# S02.net
KiCad netlist of a schematic drawn in Altium Designer
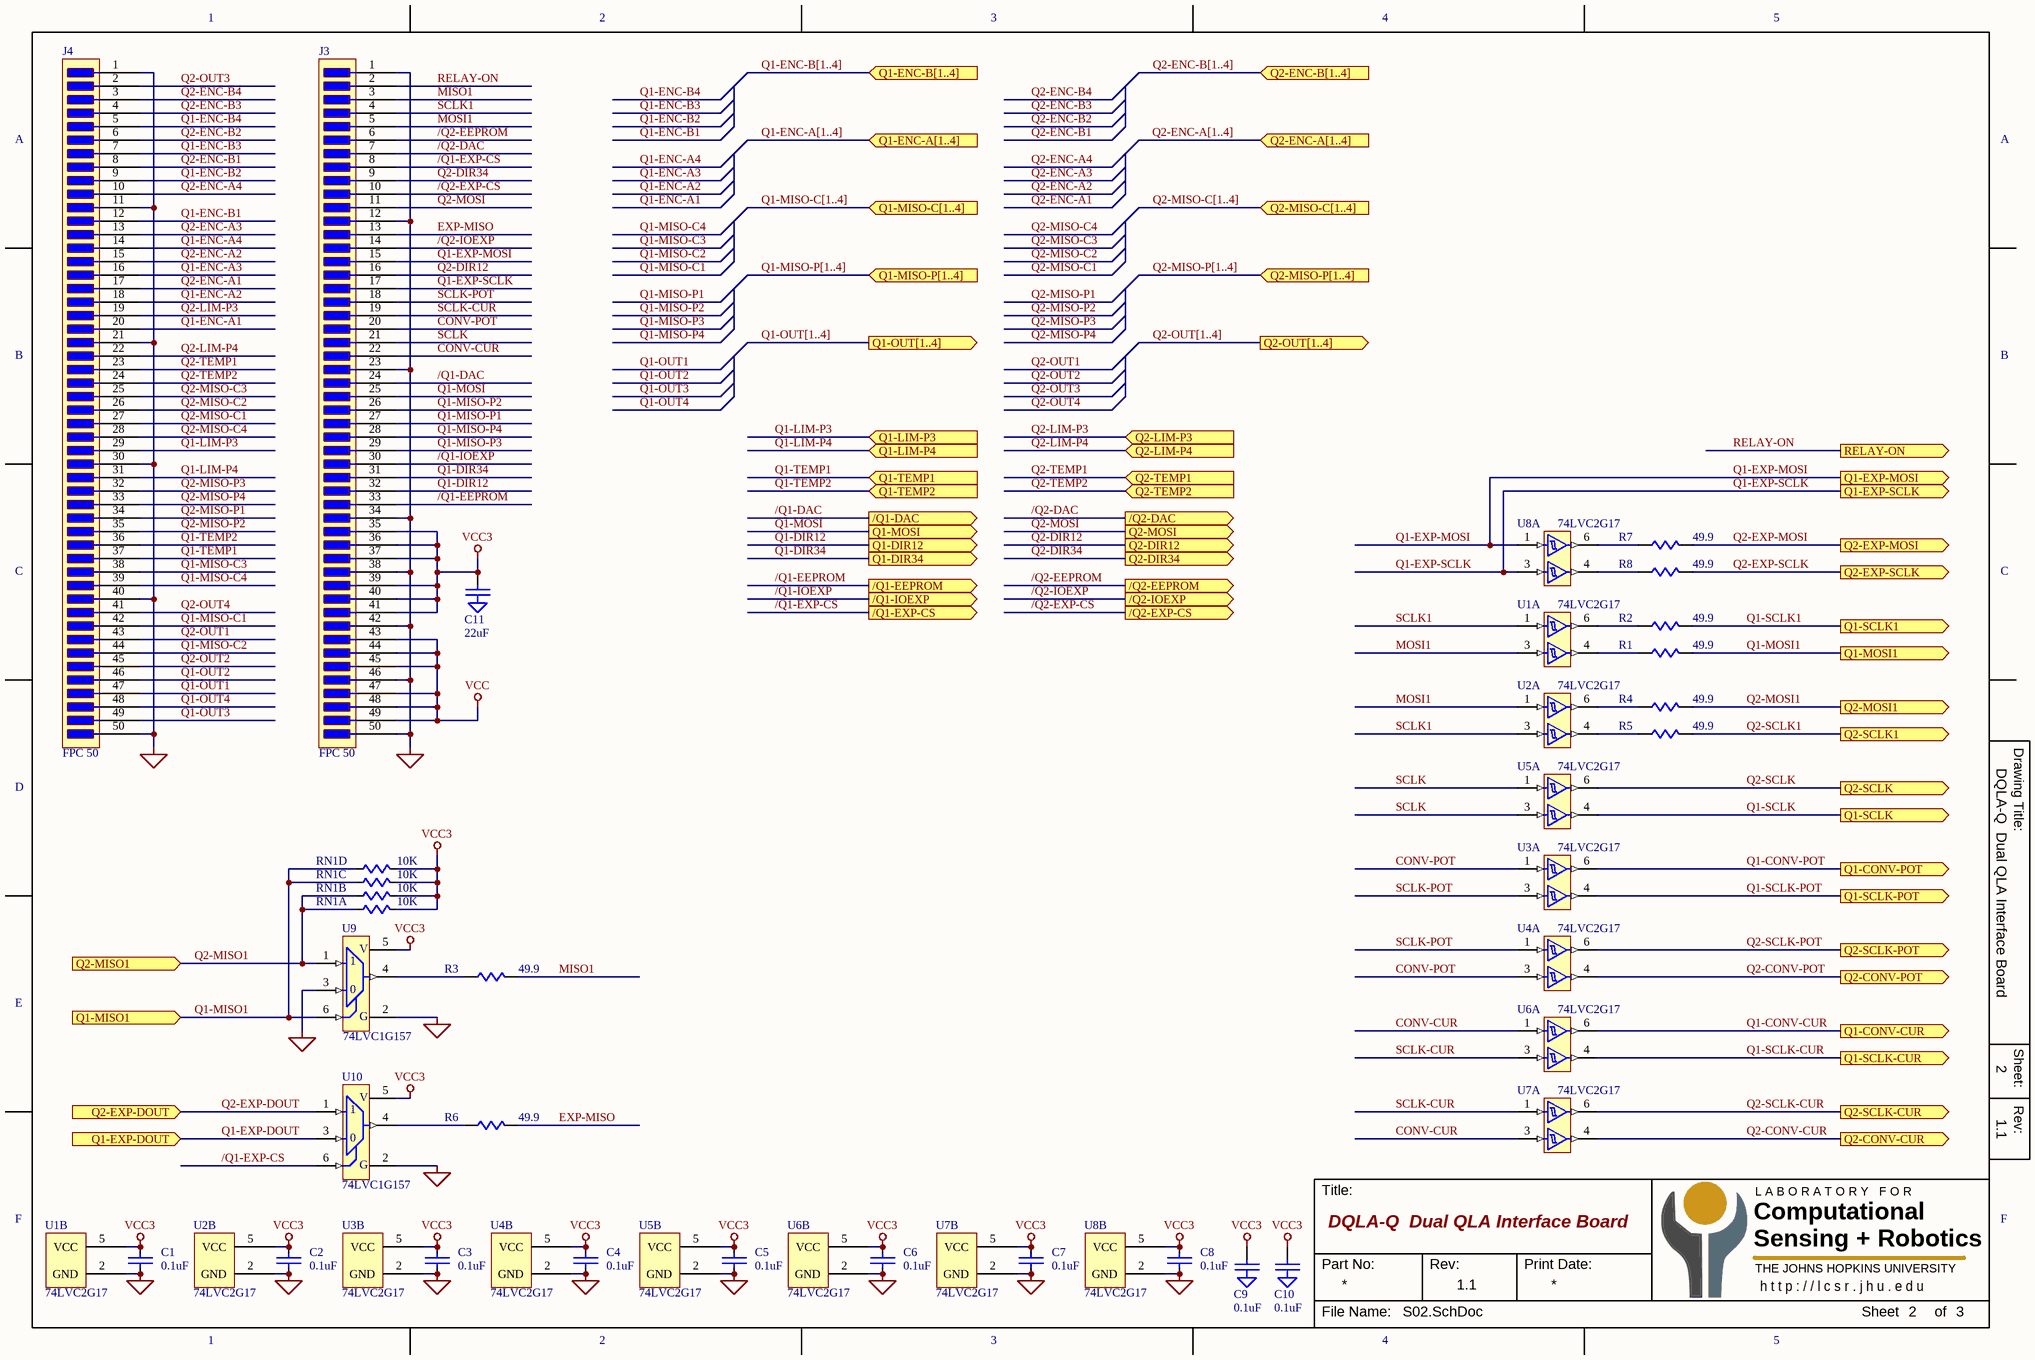
[diagram p0: S02.SchDoc]

(export (version "E")
  (design (tool "Eeschema 10.0.6"))
  (components
    (comp (ref "C1") (value "0.1uF") (footprint "C0402") (libsource (lib "LibJHU") (part "CAP")))
    (comp (ref "C2") (value "0.1uF") (footprint "C0402") (libsource (lib "LibJHU") (part "CAP")))
    (comp (ref "C3") (value "0.1uF") (footprint "C0402") (libsource (lib "LibJHU") (part "CAP")))
    (comp (ref "C4") (value "0.1uF") (footprint "C0402") (libsource (lib "LibJHU") (part "CAP")))
    (comp (ref "C5") (value "0.1uF") (footprint "C0402") (libsource (lib "LibJHU") (part "CAP")))
    (comp (ref "C6") (value "0.1uF") (footprint "C0402") (libsource (lib "LibJHU") (part "CAP")))
    (comp (ref "C7") (value "0.1uF") (footprint "C0402") (libsource (lib "LibJHU") (part "CAP")))
    (comp (ref "C8") (value "0.1uF") (footprint "C0402") (libsource (lib "LibJHU") (part "CAP")))
    (comp (ref "C9") (value "0.1uF") (footprint "C0402") (libsource (lib "LibJHU") (part "CAP-GND")))
    (comp (ref "C10") (value "0.1uF") (footprint "C0402") (libsource (lib "LibJHU") (part "CAP-GND")))
    (comp (ref "C11") (value "22uF") (footprint "C0805") (libsource (lib "LibJHU") (part "CAP-GND")))
    (comp (ref "J3")
      (value "FPC 50")
      (footprint "CONN-XF3M1-5015-1B")
      (libsource (lib "LibJHU") (part "FPC 50"))
    )
    (comp (ref "J4")
      (value "FPC 50")
      (footprint "CONN-XF3M1-5015-1B")
      (libsource (lib "LibJHU") (part "FPC 50"))
    )
    (comp (ref "R1") (value "49.9") (footprint "R0402") (libsource (lib "LibJHU") (part "R")))
    (comp (ref "R2") (value "49.9") (footprint "R0402") (libsource (lib "LibJHU") (part "R")))
    (comp (ref "R3") (value "49.9") (footprint "R0402") (libsource (lib "LibJHU") (part "R")))
    (comp (ref "R4") (value "49.9") (footprint "R0402") (libsource (lib "LibJHU") (part "R")))
    (comp (ref "R5") (value "49.9") (footprint "R0402") (libsource (lib "LibJHU") (part "R")))
    (comp (ref "R6") (value "49.9") (footprint "R0402") (libsource (lib "LibJHU") (part "R")))
    (comp (ref "R7") (value "49.9") (footprint "R0402") (libsource (lib "LibJHU") (part "R")))
    (comp (ref "R8") (value "49.9") (footprint "R0402") (libsource (lib "LibJHU") (part "R")))
    (comp (ref "RN1")
      (value "10K")
      (footprint "RN-742C083")
      (libsource (lib "LibJHU") (part "RN-DISC-SM-4X"))
    )
    (comp (ref "U1")
      (value "74LVC2G17")
      (footprint "SC70-6")
      (description "NC7WZ17")
      (libsource (lib "LibJHU") (part "2G17-2"))
    )
    (comp (ref "U2")
      (value "74LVC2G17")
      (footprint "SC70-6")
      (description "NC7WZ17")
      (libsource (lib "LibJHU") (part "2G17-2"))
    )
    (comp (ref "U3")
      (value "74LVC2G17")
      (footprint "SC70-6")
      (description "NC7WZ17")
      (libsource (lib "LibJHU") (part "2G17-2"))
    )
    (comp (ref "U4")
      (value "74LVC2G17")
      (footprint "SC70-6")
      (description "NC7WZ17")
      (libsource (lib "LibJHU") (part "2G17-2"))
    )
    (comp (ref "U5")
      (value "74LVC2G17")
      (footprint "SC70-6")
      (description "NC7WZ17")
      (libsource (lib "LibJHU") (part "2G17-2"))
    )
    (comp (ref "U6")
      (value "74LVC2G17")
      (footprint "SC70-6")
      (description "NC7WZ17")
      (libsource (lib "LibJHU") (part "2G17-2"))
    )
    (comp (ref "U7")
      (value "74LVC2G17")
      (footprint "SC70-6")
      (description "NC7WZ17")
      (libsource (lib "LibJHU") (part "2G17-2"))
    )
    (comp (ref "U8")
      (value "74LVC2G17")
      (footprint "SC70-6")
      (description "NC7WZ17")
      (libsource (lib "LibJHU") (part "2G17-2"))
    )
    (comp (ref "U9") (value "74LVC1G157") (footprint "SC70-6") (libsource (lib "LibJHU") (part "1G157")))
    (comp (ref "U10") (value "74LVC1G157") (footprint "SC70-6") (libsource (lib "LibJHU") (part "1G157")))
  )
  (nets
    (net (code "1") (name "/CONV-CUR") (class "Default")
      (node (ref "J3") (pin "22") (pinfunction "22_22") (pintype "passive"))
      (node (ref "U6") (pin "1") (pintype "input"))
      (node (ref "U7") (pin "3") (pintype "input"))
    )
    (net (code "2") (name "/CONV-POT") (class "Default")
      (node (ref "J3") (pin "20") (pinfunction "20_20") (pintype "passive"))
      (node (ref "U3") (pin "1") (pintype "input"))
      (node (ref "U4") (pin "3") (pintype "input"))
    )
    (net (code "3") (name "/EXP-MISO") (class "Default")
      (node (ref "J3") (pin "13") (pinfunction "13_13") (pintype "passive"))
      (node (ref "R6") (pin "2") (pinfunction "2_2") (pintype "passive"))
    )
    (net (code "4") (name "/MISO1") (class "Default")
      (node (ref "J3") (pin "3") (pinfunction "3_3") (pintype "passive"))
      (node (ref "R3") (pin "2") (pinfunction "2_2") (pintype "passive"))
    )
    (net (code "5") (name "/MOSI1") (class "Default")
      (node (ref "J3") (pin "5") (pinfunction "5_5") (pintype "passive"))
      (node (ref "U1") (pin "3") (pintype "input"))
      (node (ref "U2") (pin "1") (pintype "input"))
    )
    (net (code "6") (name "/Q1-CONV-CUR") (class "Default") (node (ref "U6") (pin "6") (pintype "output")))
    (net (code "7") (name "/Q1-CONV-POT") (class "Default") (node (ref "U3") (pin "6") (pintype "output")))
    (net (code "8") (name "/Q1-DIR12") (class "Default")
      (node (ref "J3") (pin "32") (pinfunction "32_32") (pintype "passive"))
    )
    (net (code "9") (name "/Q1-DIR34") (class "Default")
      (node (ref "J3") (pin "31") (pinfunction "31_31") (pintype "passive"))
    )
    (net (code "10") (name "/Q1-ENC-A1") (class "Default")
      (node (ref "J4") (pin "20") (pinfunction "20_20") (pintype "passive"))
    )
    (net (code "11") (name "/Q1-ENC-A2") (class "Default")
      (node (ref "J4") (pin "18") (pinfunction "18_18") (pintype "passive"))
    )
    (net (code "12") (name "/Q1-ENC-A3") (class "Default")
      (node (ref "J4") (pin "16") (pinfunction "16_16") (pintype "passive"))
    )
    (net (code "13") (name "/Q1-ENC-A4") (class "Default")
      (node (ref "J4") (pin "14") (pinfunction "14_14") (pintype "passive"))
    )
    (net (code "15") (name "/Q1-ENC-B1") (class "Default")
      (node (ref "J4") (pin "12") (pinfunction "12_12") (pintype "passive"))
    )
    (net (code "16") (name "/Q1-ENC-B2") (class "Default")
      (node (ref "J4") (pin "9") (pinfunction "9_9") (pintype "passive"))
    )
    (net (code "17") (name "/Q1-ENC-B3") (class "Default")
      (node (ref "J4") (pin "7") (pinfunction "7_7") (pintype "passive"))
    )
    (net (code "18") (name "/Q1-ENC-B4") (class "Default")
      (node (ref "J4") (pin "5") (pinfunction "5_5") (pintype "passive"))
    )
    (net (code "20") (name "/Q1-EXP-DOUT") (class "Default") (node (ref "U10") (pin "3") (pintype "input")))
    (net (code "21") (name "/Q1-EXP-MOSI") (class "Default")
      (node (ref "J3") (pin "15") (pinfunction "15_15") (pintype "passive"))
      (node (ref "U8") (pin "1") (pintype "input"))
    )
    (net (code "22") (name "/Q1-EXP-SCLK") (class "Default")
      (node (ref "J3") (pin "17") (pinfunction "17_17") (pintype "passive"))
      (node (ref "U8") (pin "3") (pintype "input"))
    )
    (net (code "23") (name "/Q1-LIM-P3") (class "Default")
      (node (ref "J4") (pin "29") (pinfunction "29_29") (pintype "passive"))
    )
    (net (code "24") (name "/Q1-LIM-P4") (class "Default")
      (node (ref "J4") (pin "31") (pinfunction "31_31") (pintype "passive"))
    )
    (net (code "25") (name "/Q1-MISO-C1") (class "Default")
      (node (ref "J4") (pin "42") (pinfunction "42_42") (pintype "passive"))
    )
    (net (code "26") (name "/Q1-MISO-C2") (class "Default")
      (node (ref "J4") (pin "44") (pinfunction "44_44") (pintype "passive"))
    )
    (net (code "27") (name "/Q1-MISO-C3") (class "Default")
      (node (ref "J4") (pin "38") (pinfunction "38_38") (pintype "passive"))
    )
    (net (code "28") (name "/Q1-MISO-C4") (class "Default")
      (node (ref "J4") (pin "39") (pinfunction "39_39") (pintype "passive"))
    )
    (net (code "30") (name "/Q1-MISO-P1") (class "Default")
      (node (ref "J3") (pin "27") (pinfunction "27_27") (pintype "passive"))
    )
    (net (code "31") (name "/Q1-MISO-P2") (class "Default")
      (node (ref "J3") (pin "26") (pinfunction "26_26") (pintype "passive"))
    )
    (net (code "32") (name "/Q1-MISO-P3") (class "Default")
      (node (ref "J3") (pin "29") (pinfunction "29_29") (pintype "passive"))
    )
    (net (code "33") (name "/Q1-MISO-P4") (class "Default")
      (node (ref "J3") (pin "28") (pinfunction "28_28") (pintype "passive"))
    )
    (net (code "35") (name "/Q1-MISO1") (class "Default")
      (node (ref "RN1") (pin "3") (pinfunction "3_3") (pintype "passive"))
      (node (ref "RN1") (pin "4") (pinfunction "4_4") (pintype "passive"))
      (node (ref "U9") (pin "6") (pintype "input"))
    )
    (net (code "36") (name "/Q1-MOSI") (class "Default")
      (node (ref "J3") (pin "25") (pinfunction "25_25") (pintype "passive"))
    )
    (net (code "37") (name "/Q1-MOSI1") (class "Default")
      (node (ref "R1") (pin "2") (pinfunction "2_2") (pintype "passive"))
    )
    (net (code "38") (name "/Q1-OUT1") (class "Default")
      (node (ref "J4") (pin "47") (pinfunction "47_47") (pintype "passive"))
    )
    (net (code "39") (name "/Q1-OUT2") (class "Default")
      (node (ref "J4") (pin "46") (pinfunction "46_46") (pintype "passive"))
    )
    (net (code "40") (name "/Q1-OUT3") (class "Default")
      (node (ref "J4") (pin "49") (pinfunction "49_49") (pintype "passive"))
    )
    (net (code "41") (name "/Q1-OUT4") (class "Default")
      (node (ref "J4") (pin "48") (pinfunction "48_48") (pintype "passive"))
    )
    (net (code "43") (name "/Q1-SCLK") (class "Default") (node (ref "U5") (pin "4") (pintype "output")))
    (net (code "44") (name "/Q1-SCLK-CUR") (class "Default") (node (ref "U6") (pin "4") (pintype "output")))
    (net (code "45") (name "/Q1-SCLK-POT") (class "Default") (node (ref "U3") (pin "4") (pintype "output")))
    (net (code "46") (name "/Q1-SCLK1") (class "Default")
      (node (ref "R2") (pin "2") (pinfunction "2_2") (pintype "passive"))
    )
    (net (code "47") (name "/Q1-TEMP1") (class "Default")
      (node (ref "J4") (pin "37") (pinfunction "37_37") (pintype "passive"))
    )
    (net (code "48") (name "/Q1-TEMP2") (class "Default")
      (node (ref "J4") (pin "36") (pinfunction "36_36") (pintype "passive"))
    )
    (net (code "49") (name "/Q2-CONV-CUR") (class "Default") (node (ref "U7") (pin "4") (pintype "output")))
    (net (code "50") (name "/Q2-CONV-POT") (class "Default") (node (ref "U4") (pin "4") (pintype "output")))
    (net (code "51") (name "/Q2-DIR12") (class "Default")
      (node (ref "J3") (pin "16") (pinfunction "16_16") (pintype "passive"))
    )
    (net (code "52") (name "/Q2-DIR34") (class "Default")
      (node (ref "J3") (pin "9") (pinfunction "9_9") (pintype "passive"))
    )
    (net (code "53") (name "/Q2-ENC-A1") (class "Default")
      (node (ref "J4") (pin "17") (pinfunction "17_17") (pintype "passive"))
    )
    (net (code "54") (name "/Q2-ENC-A2") (class "Default")
      (node (ref "J4") (pin "15") (pinfunction "15_15") (pintype "passive"))
    )
    (net (code "55") (name "/Q2-ENC-A3") (class "Default")
      (node (ref "J4") (pin "13") (pinfunction "13_13") (pintype "passive"))
    )
    (net (code "56") (name "/Q2-ENC-A4") (class "Default")
      (node (ref "J4") (pin "10") (pinfunction "10_10") (pintype "passive"))
    )
    (net (code "58") (name "/Q2-ENC-B1") (class "Default")
      (node (ref "J4") (pin "8") (pinfunction "8_8") (pintype "passive"))
    )
    (net (code "59") (name "/Q2-ENC-B2") (class "Default")
      (node (ref "J4") (pin "6") (pinfunction "6_6") (pintype "passive"))
    )
    (net (code "60") (name "/Q2-ENC-B3") (class "Default")
      (node (ref "J4") (pin "4") (pinfunction "4_4") (pintype "passive"))
    )
    (net (code "61") (name "/Q2-ENC-B4") (class "Default")
      (node (ref "J4") (pin "3") (pinfunction "3_3") (pintype "passive"))
    )
    (net (code "63") (name "/Q2-EXP-DOUT") (class "Default") (node (ref "U10") (pin "1") (pintype "input")))
    (net (code "64") (name "/Q2-EXP-MOSI") (class "Default")
      (node (ref "R7") (pin "2") (pinfunction "2_2") (pintype "passive"))
    )
    (net (code "65") (name "/Q2-EXP-SCLK") (class "Default")
      (node (ref "R8") (pin "2") (pinfunction "2_2") (pintype "passive"))
    )
    (net (code "66") (name "/Q2-LIM-P3") (class "Default")
      (node (ref "J4") (pin "19") (pinfunction "19_19") (pintype "passive"))
    )
    (net (code "67") (name "/Q2-LIM-P4") (class "Default")
      (node (ref "J4") (pin "22") (pinfunction "22_22") (pintype "passive"))
    )
    (net (code "68") (name "/Q2-MISO-C1") (class "Default")
      (node (ref "J4") (pin "27") (pinfunction "27_27") (pintype "passive"))
    )
    (net (code "69") (name "/Q2-MISO-C2") (class "Default")
      (node (ref "J4") (pin "26") (pinfunction "26_26") (pintype "passive"))
    )
    (net (code "70") (name "/Q2-MISO-C3") (class "Default")
      (node (ref "J4") (pin "25") (pinfunction "25_25") (pintype "passive"))
    )
    (net (code "71") (name "/Q2-MISO-C4") (class "Default")
      (node (ref "J4") (pin "28") (pinfunction "28_28") (pintype "passive"))
    )
    (net (code "73") (name "/Q2-MISO-P1") (class "Default")
      (node (ref "J4") (pin "34") (pinfunction "34_34") (pintype "passive"))
    )
    (net (code "74") (name "/Q2-MISO-P2") (class "Default")
      (node (ref "J4") (pin "35") (pinfunction "35_35") (pintype "passive"))
    )
    (net (code "75") (name "/Q2-MISO-P3") (class "Default")
      (node (ref "J4") (pin "32") (pinfunction "32_32") (pintype "passive"))
    )
    (net (code "76") (name "/Q2-MISO-P4") (class "Default")
      (node (ref "J4") (pin "33") (pinfunction "33_33") (pintype "passive"))
    )
    (net (code "78") (name "/Q2-MISO1") (class "Default")
      (node (ref "RN1") (pin "1") (pinfunction "1_1") (pintype "passive"))
      (node (ref "RN1") (pin "2") (pinfunction "2_2") (pintype "passive"))
      (node (ref "U9") (pin "1") (pintype "input"))
    )
    (net (code "79") (name "/Q2-MOSI") (class "Default")
      (node (ref "J3") (pin "11") (pinfunction "11_11") (pintype "passive"))
    )
    (net (code "80") (name "/Q2-MOSI1") (class "Default")
      (node (ref "R4") (pin "2") (pinfunction "2_2") (pintype "passive"))
    )
    (net (code "81") (name "/Q2-OUT1") (class "Default")
      (node (ref "J4") (pin "43") (pinfunction "43_43") (pintype "passive"))
    )
    (net (code "82") (name "/Q2-OUT2") (class "Default")
      (node (ref "J4") (pin "45") (pinfunction "45_45") (pintype "passive"))
    )
    (net (code "83") (name "/Q2-OUT3") (class "Default")
      (node (ref "J4") (pin "2") (pinfunction "2_2") (pintype "passive"))
    )
    (net (code "84") (name "/Q2-OUT4") (class "Default")
      (node (ref "J4") (pin "41") (pinfunction "41_41") (pintype "passive"))
    )
    (net (code "86") (name "/Q2-SCLK") (class "Default") (node (ref "U5") (pin "6") (pintype "output")))
    (net (code "87") (name "/Q2-SCLK-CUR") (class "Default") (node (ref "U7") (pin "6") (pintype "output")))
    (net (code "88") (name "/Q2-SCLK-POT") (class "Default") (node (ref "U4") (pin "6") (pintype "output")))
    (net (code "89") (name "/Q2-SCLK1") (class "Default")
      (node (ref "R5") (pin "2") (pinfunction "2_2") (pintype "passive"))
    )
    (net (code "90") (name "/Q2-TEMP1") (class "Default")
      (node (ref "J4") (pin "23") (pinfunction "23_23") (pintype "passive"))
    )
    (net (code "91") (name "/Q2-TEMP2") (class "Default")
      (node (ref "J4") (pin "24") (pinfunction "24_24") (pintype "passive"))
    )
    (net (code "92") (name "/RELAY-ON") (class "Default")
      (node (ref "J3") (pin "2") (pinfunction "2_2") (pintype "passive"))
    )
    (net (code "93") (name "/SCLK") (class "Default")
      (node (ref "J3") (pin "21") (pinfunction "21_21") (pintype "passive"))
      (node (ref "U5") (pin "1") (pintype "input"))
      (node (ref "U5") (pin "3") (pintype "input"))
    )
    (net (code "94") (name "/SCLK-CUR") (class "Default")
      (node (ref "J3") (pin "19") (pinfunction "19_19") (pintype "passive"))
      (node (ref "U6") (pin "3") (pintype "input"))
      (node (ref "U7") (pin "1") (pintype "input"))
    )
    (net (code "95") (name "/SCLK-POT") (class "Default")
      (node (ref "J3") (pin "18") (pinfunction "18_18") (pintype "passive"))
      (node (ref "U3") (pin "3") (pintype "input"))
      (node (ref "U4") (pin "1") (pintype "input"))
    )
    (net (code "96") (name "/SCLK1") (class "Default")
      (node (ref "J3") (pin "4") (pinfunction "4_4") (pintype "passive"))
      (node (ref "U1") (pin "1") (pintype "input"))
      (node (ref "U2") (pin "3") (pintype "input"))
    )
    (net (code "97") (name "/{slash}Q1-DAC") (class "Default")
      (node (ref "J3") (pin "24") (pinfunction "24_24") (pintype "passive"))
    )
    (net (code "98") (name "/{slash}Q1-EEPROM") (class "Default")
      (node (ref "J3") (pin "33") (pinfunction "33_33") (pintype "passive"))
    )
    (net (code "99") (name "/{slash}Q1-EXP-CS") (class "Default")
      (node (ref "J3") (pin "8") (pinfunction "8_8") (pintype "passive"))
      (node (ref "U10") (pin "6") (pintype "input"))
    )
    (net (code "100") (name "/{slash}Q1-IOEXP") (class "Default")
      (node (ref "J3") (pin "30") (pinfunction "30_30") (pintype "passive"))
    )
    (net (code "101") (name "/{slash}Q2-DAC") (class "Default")
      (node (ref "J3") (pin "7") (pinfunction "7_7") (pintype "passive"))
    )
    (net (code "102") (name "/{slash}Q2-EEPROM") (class "Default")
      (node (ref "J3") (pin "6") (pinfunction "6_6") (pintype "passive"))
    )
    (net (code "103") (name "/{slash}Q2-EXP-CS") (class "Default")
      (node (ref "J3") (pin "10") (pinfunction "10_10") (pintype "passive"))
    )
    (net (code "104") (name "/{slash}Q2-IOEXP") (class "Default")
      (node (ref "J3") (pin "14") (pinfunction "14_14") (pintype "passive"))
    )
    (net (code "105") (name "GND") (class "Default")
      (node (ref "C1") (pin "2") (pintype "passive"))
      (node (ref "C10") (pin "2") (pinfunction "GND_2") (pintype "power_in"))
      (node (ref "C11") (pin "2") (pinfunction "GND_2") (pintype "power_in"))
      (node (ref "C2") (pin "2") (pintype "passive"))
      (node (ref "C3") (pin "2") (pintype "passive"))
      (node (ref "C4") (pin "2") (pintype "passive"))
      (node (ref "C5") (pin "2") (pintype "passive"))
      (node (ref "C6") (pin "2") (pintype "passive"))
      (node (ref "C7") (pin "2") (pintype "passive"))
      (node (ref "C8") (pin "2") (pintype "passive"))
      (node (ref "C9") (pin "2") (pinfunction "GND_2") (pintype "power_in"))
      (node (ref "J3") (pin "1") (pinfunction "1_1") (pintype "passive"))
      (node (ref "J3") (pin "12") (pinfunction "12_12") (pintype "passive"))
      (node (ref "J3") (pin "23") (pinfunction "23_23") (pintype "passive"))
      (node (ref "J3") (pin "34") (pinfunction "34_34") (pintype "passive"))
      (node (ref "J3") (pin "38") (pinfunction "38_38") (pintype "passive"))
      (node (ref "J3") (pin "42") (pinfunction "42_42") (pintype "passive"))
      (node (ref "J3") (pin "46") (pinfunction "46_46") (pintype "passive"))
      (node (ref "J3") (pin "50") (pinfunction "50_50") (pintype "passive"))
      (node (ref "J4") (pin "1") (pinfunction "1_1") (pintype "passive"))
      (node (ref "J4") (pin "11") (pinfunction "11_11") (pintype "passive"))
      (node (ref "J4") (pin "21") (pinfunction "21_21") (pintype "passive"))
      (node (ref "J4") (pin "30") (pinfunction "30_30") (pintype "passive"))
      (node (ref "J4") (pin "40") (pinfunction "40_40") (pintype "passive"))
      (node (ref "J4") (pin "50") (pinfunction "50_50") (pintype "passive"))
      (node (ref "U1") (pin "2") (pinfunction "GND_2") (pintype "power_in"))
      (node (ref "U10") (pin "2") (pinfunction "-_2") (pintype "power_in"))
      (node (ref "U2") (pin "2") (pinfunction "GND_2") (pintype "power_in"))
      (node (ref "U3") (pin "2") (pinfunction "GND_2") (pintype "power_in"))
      (node (ref "U4") (pin "2") (pinfunction "GND_2") (pintype "power_in"))
      (node (ref "U5") (pin "2") (pinfunction "GND_2") (pintype "power_in"))
      (node (ref "U6") (pin "2") (pinfunction "GND_2") (pintype "power_in"))
      (node (ref "U7") (pin "2") (pinfunction "GND_2") (pintype "power_in"))
      (node (ref "U8") (pin "2") (pinfunction "GND_2") (pintype "power_in"))
      (node (ref "U9") (pin "2") (pinfunction "-_2") (pintype "power_in"))
      (node (ref "U9") (pin "3") (pintype "input"))
    )
    (net (code "106") (name "Net-(R1-Pad1)") (class "Default")
      (node (ref "R1") (pin "1") (pinfunction "1_1") (pintype "passive"))
      (node (ref "U1") (pin "4") (pintype "output"))
    )
    (net (code "107") (name "Net-(R2-Pad1)") (class "Default")
      (node (ref "R2") (pin "1") (pinfunction "1_1") (pintype "passive"))
      (node (ref "U1") (pin "6") (pintype "output"))
    )
    (net (code "108") (name "Net-(R3-Pad1)") (class "Default")
      (node (ref "R3") (pin "1") (pinfunction "1_1") (pintype "passive"))
      (node (ref "U9") (pin "4") (pintype "output"))
    )
    (net (code "109") (name "Net-(R4-Pad1)") (class "Default")
      (node (ref "R4") (pin "1") (pinfunction "1_1") (pintype "passive"))
      (node (ref "U2") (pin "6") (pintype "output"))
    )
    (net (code "110") (name "Net-(R5-Pad1)") (class "Default")
      (node (ref "R5") (pin "1") (pinfunction "1_1") (pintype "passive"))
      (node (ref "U2") (pin "4") (pintype "output"))
    )
    (net (code "111") (name "Net-(R6-Pad1)") (class "Default")
      (node (ref "R6") (pin "1") (pinfunction "1_1") (pintype "passive"))
      (node (ref "U10") (pin "4") (pintype "output"))
    )
    (net (code "112") (name "Net-(R7-Pad1)") (class "Default")
      (node (ref "R7") (pin "1") (pinfunction "1_1") (pintype "passive"))
      (node (ref "U8") (pin "6") (pintype "output"))
    )
    (net (code "113") (name "Net-(R8-Pad1)") (class "Default")
      (node (ref "R8") (pin "1") (pinfunction "1_1") (pintype "passive"))
      (node (ref "U8") (pin "4") (pintype "output"))
    )
    (net (code "114") (name "VCC") (class "Default")
      (node (ref "J3") (pin "43") (pinfunction "43_43") (pintype "passive"))
      (node (ref "J3") (pin "44") (pinfunction "44_44") (pintype "passive"))
      (node (ref "J3") (pin "45") (pinfunction "45_45") (pintype "passive"))
      (node (ref "J3") (pin "47") (pinfunction "47_47") (pintype "passive"))
      (node (ref "J3") (pin "48") (pinfunction "48_48") (pintype "passive"))
      (node (ref "J3") (pin "49") (pinfunction "49_49") (pintype "passive"))
    )
    (net (code "115") (name "VCC3") (class "Default")
      (node (ref "C1") (pin "1") (pintype "passive"))
      (node (ref "C10") (pin "1") (pintype "passive"))
      (node (ref "C11") (pin "1") (pintype "passive"))
      (node (ref "C2") (pin "1") (pintype "passive"))
      (node (ref "C3") (pin "1") (pintype "passive"))
      (node (ref "C4") (pin "1") (pintype "passive"))
      (node (ref "C5") (pin "1") (pintype "passive"))
      (node (ref "C6") (pin "1") (pintype "passive"))
      (node (ref "C7") (pin "1") (pintype "passive"))
      (node (ref "C8") (pin "1") (pintype "passive"))
      (node (ref "C9") (pin "1") (pintype "passive"))
      (node (ref "J3") (pin "35") (pinfunction "35_35") (pintype "passive"))
      (node (ref "J3") (pin "36") (pinfunction "36_36") (pintype "passive"))
      (node (ref "J3") (pin "37") (pinfunction "37_37") (pintype "passive"))
      (node (ref "J3") (pin "39") (pinfunction "39_39") (pintype "passive"))
      (node (ref "J3") (pin "40") (pinfunction "40_40") (pintype "passive"))
      (node (ref "J3") (pin "41") (pinfunction "41_41") (pintype "passive"))
      (node (ref "RN1") (pin "5") (pinfunction "5_5") (pintype "passive"))
      (node (ref "RN1") (pin "6") (pinfunction "6_6") (pintype "passive"))
      (node (ref "RN1") (pin "7") (pinfunction "7_7") (pintype "passive"))
      (node (ref "RN1") (pin "8") (pinfunction "8_8") (pintype "passive"))
      (node (ref "U1") (pin "5") (pinfunction "VCC_5") (pintype "power_in"))
      (node (ref "U10") (pin "5") (pinfunction "+_5") (pintype "power_in"))
      (node (ref "U2") (pin "5") (pinfunction "VCC_5") (pintype "power_in"))
      (node (ref "U3") (pin "5") (pinfunction "VCC_5") (pintype "power_in"))
      (node (ref "U4") (pin "5") (pinfunction "VCC_5") (pintype "power_in"))
      (node (ref "U5") (pin "5") (pinfunction "VCC_5") (pintype "power_in"))
      (node (ref "U6") (pin "5") (pinfunction "VCC_5") (pintype "power_in"))
      (node (ref "U7") (pin "5") (pinfunction "VCC_5") (pintype "power_in"))
      (node (ref "U8") (pin "5") (pinfunction "VCC_5") (pintype "power_in"))
      (node (ref "U9") (pin "5") (pinfunction "+_5") (pintype "power_in"))
    )
  )
)
